# main.net
KiCad netlist of a schematic drawn in Altium Designer
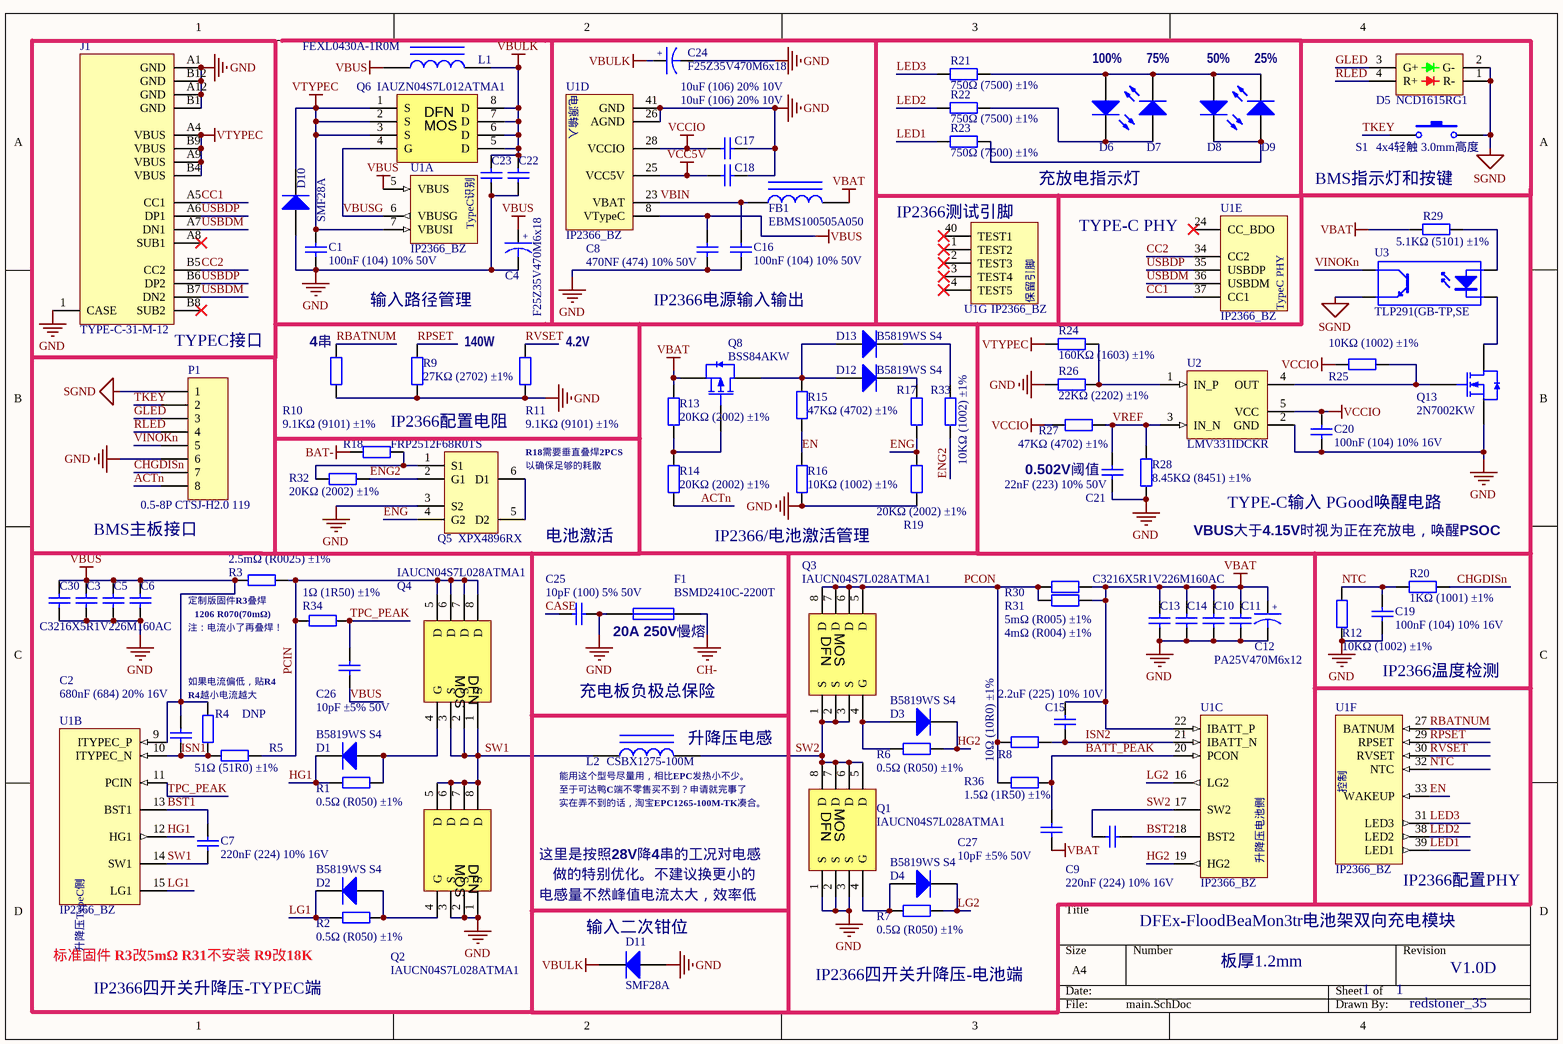
[diagram p0: main.SchDoc]

(export (version "E")
  (design (tool "Eeschema 10.0.6"))
  (components
    (comp (ref "C1")
      (value "100nF (104) 10% 50V")
      (footprint "0402_C")
      (description "贴片电容")
      (libsource (lib "Miscellaneous Devices LC") (part "0402 100nF (104) 10% 16V"))
    )
    (comp (ref "C2")
      (value "680nF (684) 20% 16V")
      (footprint "0402_C")
      (description "贴片电容")
      (libsource (lib "Miscellaneous Devices LC") (part "0402 470nF (474) 10% 10V"))
    )
    (comp (ref "C3")
      (value "C3216X5R1V226M160AC")
      (footprint "1206C")
      (description "1206尺寸TDK MLCC 35V 22uF")
      (fields (field (name "PUBLISHER") "Altium Limited"))
      (libsource (lib "山猫的集成库20190318") (part "Cap"))
    )
    (comp (ref "C4")
      (value "F25Z35V470M6x18")
      (footprint "ElecCap_Hori")
      (description "直插艾华固态电容，耐压35V容量470uF，尺寸D6.3x18")
      (libsource (lib "山猫的集成库20190318") (part "CAP2"))
    )
    (comp (ref "C5")
      (value "C3216X5R1V226M160AC")
      (footprint "1206C")
      (description "1206尺寸TDK MLCC 35V 22uF")
      (fields (field (name "PUBLISHER") "Altium Limited"))
      (libsource (lib "山猫的集成库20190318") (part "Cap"))
    )
    (comp (ref "C6")
      (value "C3216X5R1V226M160AC")
      (footprint "1206C")
      (description "1206尺寸TDK MLCC 35V 22uF")
      (fields (field (name "PUBLISHER") "Altium Limited"))
      (libsource (lib "山猫的集成库20190318") (part "Cap"))
    )
    (comp (ref "C7")
      (value "220nF (224) 10% 16V")
      (footprint "0402_C")
      (description "贴片电容")
      (libsource (lib "Miscellaneous Devices LC") (part "0402 220nF (224) 10% 16V"))
    )
    (comp (ref "C8")
      (value "470NF (474) 10% 50V")
      (footprint "0402_C")
      (description "贴片电容")
      (libsource (lib "Miscellaneous Devices LC") (part "0402 1.0uF (105) 10% 25V"))
    )
    (comp (ref "C9")
      (value "220nF (224) 10% 16V")
      (footprint "0402_C")
      (description "贴片电容")
      (libsource (lib "Miscellaneous Devices LC") (part "0402 220nF (224) 10% 16V"))
    )
    (comp (ref "C10")
      (value "C3216X5R1V226M160AC")
      (footprint "1206C")
      (description "1206尺寸TDK MLCC 35V 22uF")
      (fields (field (name "PUBLISHER") "Altium Limited"))
      (libsource (lib "山猫的集成库20190318") (part "Cap"))
    )
    (comp (ref "C11")
      (value "C3216X5R1V226M160AC")
      (footprint "1206C")
      (description "1206尺寸TDK MLCC 35V 22uF")
      (fields (field (name "PUBLISHER") "Altium Limited"))
      (libsource (lib "山猫的集成库20190318") (part "Cap"))
    )
    (comp (ref "C12")
      (value "PA25V470M6x12")
      (footprint "ElecCap_Hori")
      (description "直插固态电容，耐压25V容量470uF，尺寸D6.3x12")
      (libsource (lib "山猫的集成库20190318") (part "CAP2"))
    )
    (comp (ref "C13")
      (value "C3216X5R1V226M160AC")
      (footprint "1206C")
      (description "1206尺寸TDK MLCC 35V 22uF")
      (fields (field (name "PUBLISHER") "Altium Limited"))
      (libsource (lib "山猫的集成库20190318") (part "Cap"))
    )
    (comp (ref "C14")
      (value "C3216X5R1V226M160AC")
      (footprint "1206C")
      (description "1206尺寸TDK MLCC 35V 22uF")
      (fields (field (name "PUBLISHER") "Altium Limited"))
      (libsource (lib "山猫的集成库20190318") (part "Cap"))
    )
    (comp (ref "C15")
      (value "2.2uF (225) 10% 10V")
      (footprint "0402_C")
      (description "贴片电容")
      (libsource (lib "Miscellaneous Devices LC") (part "0402 1.0uF (105) 10% 25V"))
    )
    (comp (ref "C16")
      (value "100nF (104) 10% 50V")
      (footprint "0402_C")
      (description "贴片电容")
      (libsource (lib "Miscellaneous Devices LC") (part "0402 100nF (104) 10% 16V"))
    )
    (comp (ref "C17")
      (value "10uF (106) 20% 10V")
      (footprint "0402_C")
      (description "贴片电容")
      (libsource (lib "Miscellaneous Devices LC") (part "0402 10uF (106) 20% 6.3V"))
    )
    (comp (ref "C18")
      (value "10uF (106) 20% 10V")
      (footprint "0402_C")
      (description "贴片电容")
      (libsource (lib "Miscellaneous Devices LC") (part "0402 10uF (106) 20% 6.3V"))
    )
    (comp (ref "C19")
      (value "100nF (104) 10% 16V")
      (footprint "0402_C")
      (description "贴片电容")
      (libsource (lib "Miscellaneous Devices LC") (part "0402 100nF (104) 10% 16V"))
    )
    (comp (ref "C20")
      (value "100nF (104) 10% 16V")
      (footprint "0402_C")
      (description "贴片电容")
      (libsource (lib "Miscellaneous Devices LC") (part "0402 100nF (104) 10% 16V"))
    )
    (comp (ref "C21")
      (value "22nF (223) 10% 50V")
      (footprint "0402_C")
      (description "贴片电容")
      (libsource (lib "Miscellaneous Devices LC") (part "0402 22nF (223) 10% 50V"))
    )
    (comp (ref "C22")
      (value "C3216X5R1V226M160AC")
      (footprint "1206C")
      (description "1206尺寸TDK MLCC 35V 22uF")
      (fields (field (name "PUBLISHER") "Altium Limited"))
      (libsource (lib "山猫的集成库20190318") (part "Cap"))
    )
    (comp (ref "C23")
      (value "C3216X5R1V226M160AC")
      (footprint "1206C")
      (description "1206尺寸TDK MLCC 35V 22uF")
      (fields (field (name "PUBLISHER") "Altium Limited"))
      (libsource (lib "山猫的集成库20190318") (part "Cap"))
    )
    (comp (ref "C24")
      (value "F25Z35V470M6x18")
      (footprint "ElecCap_Hori")
      (description "直插艾华固态电容，耐压35V容量470uF，尺寸D6.3x18")
      (libsource (lib "山猫的集成库20190318") (part "CAP2"))
    )
    (comp (ref "C25")
      (value "10pF (100) 5% 50V")
      (footprint "0402_C")
      (description "贴片电容")
      (libsource (lib "Miscellaneous Devices LC") (part "0402 10pF (100) 5% 50V"))
    )
    (comp (ref "C26")
      (value "10pF ±5% 50V")
      (footprint "0402_C")
      (description "贴片电容")
      (libsource (lib "Miscellaneous Devices LC") (part "0402 1nF (102) 10% 50V"))
    )
    (comp (ref "C27")
      (value "10pF ±5% 50V")
      (footprint "0402_C")
      (description "贴片电容")
      (libsource (lib "Miscellaneous Devices LC") (part "0402 1nF (102) 10% 50V"))
    )
    (comp (ref "C30")
      (value "C3216X5R1V226M160AC")
      (footprint "1206C")
      (description "1206尺寸TDK MLCC 35V 22uF")
      (fields (field (name "PUBLISHER") "Altium Limited"))
      (libsource (lib "山猫的集成库20190318") (part "Cap"))
    )
    (comp (ref "D1")
      (value "B5819WS S4")
      (footprint "SOD-323")
      (description "二极管")
      (libsource (lib "Miscellaneous Devices LC") (part "SOD-323 1N4148WS T4"))
    )
    (comp (ref "D2")
      (value "B5819WS S4")
      (footprint "SOD-323")
      (description "二极管")
      (libsource (lib "Miscellaneous Devices LC") (part "SOD-323 1N4148WS T4"))
    )
    (comp (ref "D3")
      (value "B5819WS S4")
      (footprint "SOD-323")
      (description "二极管")
      (libsource (lib "Miscellaneous Devices LC") (part "SOD-323 1N4148WS T4"))
    )
    (comp (ref "D4")
      (value "B5819WS S4")
      (footprint "SOD-323")
      (description "二极管")
      (libsource (lib "Miscellaneous Devices LC") (part "SOD-323 1N4148WS T4"))
    )
    (comp (ref "D5")
      (value "NCD1615RG1")
      (footprint "LED-SMD_4P-L1.6-W1.5-TL-1")
      (description "国星光电 0606(1615) 尺寸 双色LED 红色/翠绿")
      (libsource (lib "custom") (part "0606DualColor LED"))
    )
    (comp (ref "D6")
      (value "蓝灯 0603")
      (footprint "0603_LED_S1")
      (description "发光二极管")
      (libsource (lib "Miscellaneous Devices LC") (part "0603 蓝灯"))
    )
    (comp (ref "D7")
      (value "蓝灯 0603")
      (footprint "0603_LED_S1")
      (description "发光二极管")
      (libsource (lib "Miscellaneous Devices LC") (part "0603 蓝灯"))
    )
    (comp (ref "D8")
      (value "蓝灯 0603")
      (footprint "0603_LED_S1")
      (description "发光二极管")
      (libsource (lib "Miscellaneous Devices LC") (part "0603 蓝灯"))
    )
    (comp (ref "D9")
      (value "蓝灯 0603")
      (footprint "0603_LED_S1")
      (description "发光二极管")
      (libsource (lib "Miscellaneous Devices LC") (part "0603 蓝灯"))
    )
    (comp (ref "D10")
      (value "SMF28A")
      (footprint "SOD-123")
      (description "SOD123封装单向TVS二极管 28V反向截止电压 峰值脉冲电流4.4A@10/1000us")
      (libsource (lib "Miscellaneous Devices LC") (part "SOD-123 B5819W  SL"))
    )
    (comp (ref "D11")
      (value "SMF28A")
      (footprint "SOD-123")
      (description "SOD123封装单向TVS二极管 28V反向截止电压 峰值脉冲电流4.4A@10/1000us")
      (libsource (lib "Miscellaneous Devices LC") (part "SOD-123 B5819W  SL"))
    )
    (comp (ref "D12")
      (value "B5819WS S4")
      (footprint "SOD-323")
      (description "二极管")
      (libsource (lib "Miscellaneous Devices LC") (part "SOD-323 1N4148WS T4"))
    )
    (comp (ref "D13")
      (value "B5819WS S4")
      (footprint "SOD-323")
      (description "二极管")
      (libsource (lib "Miscellaneous Devices LC") (part "SOD-323 1N4148WS T4"))
    )
    (comp (ref "F1")
      (value "BSMD2410C-2200T")
      (footprint "Fuse6126")
      (description "2410尺寸 20A 250V 一次性 慢速熔断陶瓷保险丝")
      (fields (field (name "PUBLISHER") "Altium Limited"))
      (libsource (lib "Miscellaneous Devices") (part "Fuse 1"))
    )
    (comp (ref "FB1")
      (value "EBMS100505A050")
      (footprint "0402_L")
      (description "贴片磁珠 200mA 5R±25% 100MHz")
      (libsource (lib "Miscellaneous Devices LC") (part "0402 12nH  5%"))
    )
    (comp (ref "J1")
      (value "TYPE-C-31-M-12")
      (footprint "USB-C-SMD_KH-TYPE-C-16P")
      (description "16Pin TypeC卧式贴片座子，韩国韩荣")
      (libsource (lib "custom") (part "KH-TYPEC-16P"))
    )
    (comp (ref "L1")
      (value "FEXL0430A-1R0M")
      (footprint "XAL4020-xxxME")
      (description "长江微电一体成型电感，1.0uH±20% 14.6mΩ DCR 9.8A饱和电流")
      (fields (field (name "PUBLISHER") "Altium Limited"))
      (libsource (lib "Miscellaneous Devices") (part "Inductor Iron"))
    )
    (comp (ref "L2")
      (value "CSBX1275-100M")
      (footprint "CSBX1275")
      (description "科达嘉电子扁线一体成型电感，13.8*12.8*7.3mm，10uH 21.0A 8.77mΩ")
      (fields (field (name "PUBLISHER") "Altium Limited"))
      (libsource (lib "Miscellaneous Devices") (part "Inductor Iron"))
    )
    (comp (ref "P1")
      (value "0.5-8P CTSJ-H2.0 119")
      (footprint "FPC0.5 2H-WS-8P")
      (description "FFC/FPC连接器 间距：0.5mm，P数：8P，卧贴，抽屉式上接，厚度H2.0mm")
      (fields (field (name "PUBLISHER") "Altium Limited"))
      (libsource (lib "山猫的集成库20190318") (part "CON 8"))
    )
    (comp (ref "Q1")
      (value "IAUCN04S7L028ATMA1")
      (footprint "SON/DFN5x6(MOS)")
      (description "40V, N-Ch, 2.80mΩ max, Automotive MOSFET, SSO8(5x6), OptiMOS™ 7")
      (libsource (lib "custom") (part "SON/DFN5x6 MOS"))
    )
    (comp (ref "Q2")
      (value "IAUCN04S7L028ATMA1")
      (footprint "SON/DFN5x6(MOS)")
      (description "40V, N-Ch, 2.80mΩ max, Automotive MOSFET, SSO8(5x6), OptiMOS™ 7")
      (libsource (lib "") (part "SON/DFN5x6 MOS_2"))
    )
    (comp (ref "Q3")
      (value "IAUCN04S7L028ATMA1")
      (footprint "SON/DFN5x6(MOS)")
      (description "40V, N-Ch, 2.80mΩ max, Automotive MOSFET, SSO8(5x6), OptiMOS™ 7")
      (libsource (lib "custom") (part "SON/DFN5x6 MOS"))
    )
    (comp (ref "Q4")
      (value "IAUCN04S7L028ATMA1")
      (footprint "SON/DFN5x6(MOS)")
      (description "40V, N-Ch, 2.80mΩ max, Automotive MOSFET, SSO8(5x6), OptiMOS™ 7")
      (libsource (lib "") (part "SON/DFN5x6 MOS_2"))
    )
    (comp (ref "Q5")
      (value "XPX4896RX")
      (footprint "EDFN3x3")
      (description "双N沟道MOSFET, DFN3x3 40V 45A 7.2mΩ")
      (libsource (lib "custom") (part "XPX10H03RX"))
    )
    (comp (ref "Q6")
      (value "IAUZN04S7L012ATMA1")
      (footprint "DFN-8_L3.0-W3.0-P0.65-BL")
      (description "OptiMOS 7 40V Logic Level Power MOSFET, 1.55mΩ @ 4.5V LL,S3O8(PDFN3333) Package")
      (libsource (lib "") (part "SON/DFN5x6 MOS_1"))
    )
    (comp (ref "Q8")
      (value "BSS84AKW")
      (footprint "SC70-3")
      (description "单P沟道小信号MOSFET(场效应管)")
      (libsource (lib "Miscellaneous Devices LC") (part "SI2301CDS-T1-GE3"))
    )
    (comp (ref "Q13")
      (value "2N7002KW")
      (footprint "SC70-3")
      (description "单N沟道MOSFET(场效应管)")
      (libsource (lib "Miscellaneous Devices LC") (part "2N7002 7002"))
    )
    (comp (ref "R1")
      (value "0.5Ω (R050) ±1%")
      (footprint "0603_R")
      (description "贴片电阻")
      (libsource (lib "Miscellaneous Devices LC") (part "0603 0Ω (0R0) 1%"))
    )
    (comp (ref "R2")
      (value "0.5Ω (R050) ±1%")
      (footprint "0603_R")
      (description "贴片电阻")
      (libsource (lib "Miscellaneous Devices LC") (part "0603 0Ω (0R0) 1%"))
    )
    (comp (ref "R3")
      (value "2.5mΩ (R0025) ±1%")
      (footprint "1206_R")
      (description "1206贴片合金检流电阻 2.5mΩ")
      (libsource (lib "Miscellaneous Devices LC") (part "1206 0Ω (0R0) 1%"))
    )
    (comp (ref "R4")
      (value "DNP")
      (footprint "0402_R")
      (description "贴片电阻(暂时空置)")
      (libsource (lib "Miscellaneous Devices LC") (part "0402 3.3KΩ (3301) 1%"))
    )
    (comp (ref "R5")
      (value "51Ω (51R0) ±1%")
      (footprint "0402_R")
      (description "贴片电阻")
      (libsource (lib "Miscellaneous Devices LC") (part "0402 51Ω (51R0) 1%"))
    )
    (comp (ref "R6")
      (value "0.5Ω (R050) ±1%")
      (footprint "0603_R")
      (description "贴片电阻")
      (libsource (lib "Miscellaneous Devices LC") (part "0603 0Ω (0R0) 1%"))
    )
    (comp (ref "R7")
      (value "0.5Ω (R050) ±1%")
      (footprint "0603_R")
      (description "贴片电阻")
      (libsource (lib "Miscellaneous Devices LC") (part "0603 0Ω (0R0) 1%"))
    )
    (comp (ref "R8")
      (value "10Ω (10R0) ±1%")
      (footprint "0402_R")
      (description "贴片电阻")
      (libsource (lib "Miscellaneous Devices LC") (part "0402 10Ω (10R0) 1%"))
    )
    (comp (ref "R9")
      (value "27KΩ (2702) ±1%")
      (footprint "0402_R")
      (description "贴片电阻")
      (libsource (lib "Miscellaneous Devices LC") (part "0402 18KΩ (1802) 1%"))
    )
    (comp (ref "R10")
      (value "9.1KΩ (9101) ±1%")
      (footprint "0402_R")
      (description "贴片电阻")
      (libsource (lib "Miscellaneous Devices LC") (part "0402 10KΩ (1002) 1%"))
    )
    (comp (ref "R11")
      (value "9.1KΩ (9101) ±1%")
      (footprint "0402_R")
      (description "贴片电阻")
      (libsource (lib "Miscellaneous Devices LC") (part "0402 10KΩ (1002) 1%"))
    )
    (comp (ref "R12")
      (value "10KΩ (1002) ±1%")
      (footprint "0402_R")
      (description "贴片电阻")
      (libsource (lib "Miscellaneous Devices LC") (part "0402 10KΩ (1002) 1%"))
    )
    (comp (ref "R13")
      (value "20KΩ (2002) ±1%")
      (footprint "0402_R")
      (description "贴片电阻")
      (libsource (lib "") (part "0402 20KΩ (2002) 1%_1"))
    )
    (comp (ref "R14")
      (value "20KΩ (2002) ±1%")
      (footprint "0402_R")
      (description "贴片电阻")
      (libsource (lib "") (part "0402 20KΩ (2002) 1%_1"))
    )
    (comp (ref "R15")
      (value "47KΩ (4702) ±1%")
      (footprint "0402_R")
      (description "贴片电阻")
      (libsource (lib "Miscellaneous Devices LC") (part "0402 47KΩ (4702) 1%"))
    )
    (comp (ref "R16")
      (value "10KΩ (1002) ±1%")
      (footprint "0402_R")
      (description "贴片电阻")
      (libsource (lib "Miscellaneous Devices LC") (part "0402 10KΩ (1002) 1%"))
    )
    (comp (ref "R17")
      (value "10KΩ (1002) ±1%")
      (footprint "0402_R")
      (description "贴片电阻")
      (libsource (lib "Miscellaneous Devices LC") (part "0402 10KΩ (1002) 1%"))
    )
    (comp (ref "R18")
      (value "FRP2512F68R0TS")
      (footprint "2512")
      (description "高功率2512封装厚膜电阻 68Ω ±1% 2W")
      (fields (field (name "PUBLISHER") "Altium Limited"))
      (libsource (lib "山猫的集成库20190318") (part "Res"))
    )
    (comp (ref "R19")
      (value "20KΩ (2002) ±1%")
      (footprint "0402_R")
      (description "贴片电阻")
      (libsource (lib "") (part "0402 20KΩ (2002) 1%_1"))
    )
    (comp (ref "R20")
      (value "1KΩ (1001) ±1%")
      (footprint "0402_R")
      (description "贴片电阻")
      (libsource (lib "Miscellaneous Devices LC") (part "0402 1KΩ (1001) 1%"))
    )
    (comp (ref "R21")
      (value "750Ω (7500) ±1%")
      (footprint "0402_R")
      (description "贴片电阻")
      (libsource (lib "Miscellaneous Devices LC") (part "0402 200Ω (2000) 1%"))
    )
    (comp (ref "R22")
      (value "750Ω (7500) ±1%")
      (footprint "0402_R")
      (description "贴片电阻")
      (libsource (lib "Miscellaneous Devices LC") (part "0402 200Ω (2000) 1%"))
    )
    (comp (ref "R23")
      (value "750Ω (7500) ±1%")
      (footprint "0402_R")
      (description "贴片电阻")
      (libsource (lib "Miscellaneous Devices LC") (part "0402 200Ω (2000) 1%"))
    )
    (comp (ref "R24")
      (value "160KΩ (1603) ±1%")
      (footprint "0402_R")
      (description "贴片电阻")
      (libsource (lib "Miscellaneous Devices LC") (part "0402 100KΩ (1003) 1%"))
    )
    (comp (ref "R25")
      (value "10KΩ (1002) ±1%")
      (footprint "0402_R")
      (description "贴片电阻")
      (libsource (lib "") (part "0402 10KΩ (1002) 1%_1"))
    )
    (comp (ref "R26")
      (value "22KΩ (2202) ±1%")
      (footprint "0402_R")
      (description "贴片电阻")
      (libsource (lib "Miscellaneous Devices LC") (part "0402 22KΩ (2202) 1%"))
    )
    (comp (ref "R27")
      (value "47KΩ (4702) ±1%")
      (footprint "0402_R")
      (description "贴片电阻")
      (libsource (lib "") (part "0402 47KΩ (4702) 1%_1"))
    )
    (comp (ref "R28")
      (value "8.45KΩ (8451) ±1%")
      (footprint "0402_R")
      (description "贴片电阻")
      (libsource (lib "Miscellaneous Devices LC") (part "0402 10KΩ (1002) 1%"))
    )
    (comp (ref "R29")
      (value "5.1KΩ (5101) ±1%")
      (footprint "0603_R")
      (description "贴片电阻")
      (libsource (lib "Miscellaneous Devices LC") (part "0603 4.7KΩ (4701) 1%"))
    )
    (comp (ref "R30")
      (value "5mΩ (R005) ±1%")
      (footprint "1206_R")
      (description "贴片合金检流电阻")
      (libsource (lib "Miscellaneous Devices LC") (part "1206 0Ω (0R0) 1%"))
    )
    (comp (ref "R31")
      (value "4mΩ (R004) ±1%")
      (footprint "1206_R")
      (description "贴片合金检流电阻")
      (libsource (lib "Miscellaneous Devices LC") (part "1206 0Ω (0R0) 1%"))
    )
    (comp (ref "R32")
      (value "20KΩ (2002) ±1%")
      (footprint "0402_R")
      (description "贴片电阻")
      (libsource (lib "Miscellaneous Devices LC") (part "0402 20KΩ (2002) 1%"))
    )
    (comp (ref "R33")
      (value "10KΩ (1002) ±1%")
      (footprint "0402_R")
      (description "贴片电阻")
      (libsource (lib "Miscellaneous Devices LC") (part "0402 10KΩ (1002) 1%"))
    )
    (comp (ref "R34")
      (value "1Ω (1R50) ±1%")
      (footprint "0402_R")
      (description "贴片电阻")
      (libsource (lib "") (part "0402 51Ω (51R0) 1%_1"))
    )
    (comp (ref "R36")
      (value "1.5Ω (1R50) ±1%")
      (footprint "0402_R")
      (description "贴片电阻")
      (libsource (lib "") (part "0402 51Ω (51R0) 1%_1"))
    )
    (comp (ref "S1")
      (value "4x4轻触 3.0mm高度")
      (footprint "SW-SMD_4P-L5.2-W5.2-P3.70-LS6.4")
      (description "4x4mm锅仔片结构金属轻触开关 H3.0mm")
      (fields (field (name "PUBLISHER") "Altium Limited"))
      (libsource (lib "Miscellaneous Devices") (part "SW-PB"))
    )
    (comp (ref "U1")
      (value "IP2366_BZ")
      (footprint "QFN40-IP2366")
      (description "支持多种快充协议，最高140W功率的充放电管理SoC")
      (libsource (lib "custom") (part "IP2366_BZ"))
    )
    (comp (ref "U2")
      (value "LMV331IDCKR")
      (footprint "SC70-5")
      (description "单路通用低电压比较器，2.7-5.5V，SC70-5封装")
      (libsource (lib "custom") (part "LMV331IDCKR"))
    )
    (comp (ref "U3")
      (value "TLP291(GB-TP,SE")
      (footprint "SOP127P700X210-4M")
      (description "DC输入 光电耦合隔离器 隔离电压(rms):3750V SOP-4封装")
      (fields (field (name "PUBLISHER") "Altium Limited"))
      (libsource (lib "Miscellaneous Devices") (part "Optoisolator1"))
    )
  )
  (nets
    (net (code "1") (name "/ACTn") (class "Default")
      (node (ref "P1") (pin "8") (pinfunction "8_8") (pintype "passive"))
      (node (ref "R14") (pin "1") (pinfunction "1_1") (pintype "passive"))
    )
    (net (code "2") (name "/BATT_PEAK") (class "Default")
      (node (ref "C27") (pin "2") (pinfunction "2_2") (pintype "passive"))
      (node (ref "R36") (pin "1") (pinfunction "1_1") (pintype "passive"))
      (node (ref "U1") (pin "20") (pinfunction "PCON_20") (pintype "input"))
    )
    (net (code "3") (name "/BST1") (class "Default")
      (node (ref "C7") (pin "2") (pinfunction "2_2") (pintype "passive"))
      (node (ref "U1") (pin "13") (pinfunction "BST1_13") (pintype "power_in"))
    )
    (net (code "4") (name "/BST2") (class "Default")
      (node (ref "C9") (pin "2") (pinfunction "2_2") (pintype "passive"))
      (node (ref "U1") (pin "18") (pinfunction "BST2_18") (pintype "power_in"))
    )
    (net (code "5") (name "/CASE") (class "Default")
      (node (ref "C25") (pin "1") (pinfunction "1_1") (pintype "passive"))
    )
    (net (code "6") (name "/CC1") (class "Default")
      (node (ref "J1") (pin "A5") (pinfunction "CC1_A5") (pintype "passive"))
      (node (ref "U1") (pin "37") (pinfunction "CC1_37") (pintype "passive"))
    )
    (net (code "7") (name "/CC2") (class "Default")
      (node (ref "J1") (pin "B5") (pinfunction "CC2_B5") (pintype "passive"))
      (node (ref "U1") (pin "34") (pinfunction "CC2_34") (pintype "passive"))
    )
    (net (code "8") (name "/CHGDISn") (class "Default")
      (node (ref "P1") (pin "7") (pinfunction "7_7") (pintype "passive"))
      (node (ref "R20") (pin "2") (pinfunction "2_2") (pintype "passive"))
    )
    (net (code "9") (name "/EN") (class "Default")
      (node (ref "R15") (pin "1") (pinfunction "1_1") (pintype "passive"))
      (node (ref "R16") (pin "2") (pinfunction "2_2") (pintype "passive"))
      (node (ref "U1") (pin "33") (pinfunction "WAKEUP_33") (pintype "input"))
    )
    (net (code "10") (name "/ENG") (class "Default")
      (node (ref "Q5") (pin "4") (pinfunction "G2_4") (pintype "passive"))
      (node (ref "R17") (pin "1") (pinfunction "1_1") (pintype "passive"))
      (node (ref "R19") (pin "2") (pinfunction "2_2") (pintype "passive"))
    )
    (net (code "11") (name "/ENG2") (class "Default")
      (node (ref "Q5") (pin "2") (pinfunction "G1_2") (pintype "passive"))
      (node (ref "R32") (pin "2") (pinfunction "2_2") (pintype "passive"))
      (node (ref "R33") (pin "1") (pinfunction "1_1") (pintype "passive"))
    )
    (net (code "12") (name "/GLED") (class "Default")
      (node (ref "D5") (pin "3") (pinfunction "G+_3") (pintype "passive"))
      (node (ref "P1") (pin "3") (pinfunction "3_3") (pintype "passive"))
    )
    (net (code "13") (name "/HG1") (class "Default")
      (node (ref "D1") (pin "2") (pinfunction "K_2") (pintype "passive"))
      (node (ref "R1") (pin "1") (pinfunction "1_1") (pintype "passive"))
      (node (ref "U1") (pin "12") (pinfunction "HG1_12") (pintype "output"))
    )
    (net (code "14") (name "/HG2") (class "Default")
      (node (ref "D3") (pin "2") (pinfunction "K_2") (pintype "passive"))
      (node (ref "R6") (pin "2") (pinfunction "2_2") (pintype "passive"))
      (node (ref "U1") (pin "19") (pinfunction "HG2_19") (pintype "output"))
    )
    (net (code "15") (name "/ISN1") (class "Default")
      (node (ref "C2") (pin "1") (pinfunction "1_1") (pintype "passive"))
      (node (ref "R4") (pin "1") (pinfunction "1_1") (pintype "passive"))
      (node (ref "R5") (pin "1") (pinfunction "1_1") (pintype "passive"))
      (node (ref "U1") (pin "10") (pinfunction "ITYPEC_N_10") (pintype "input"))
    )
    (net (code "16") (name "/ISN2") (class "Default")
      (node (ref "C15") (pin "1") (pinfunction "1_1") (pintype "passive"))
      (node (ref "R8") (pin "2") (pinfunction "2_2") (pintype "passive"))
      (node (ref "U1") (pin "21") (pinfunction "IBATT_N_21") (pintype "input"))
    )
    (net (code "17") (name "/LED1") (class "Default")
      (node (ref "R23") (pin "1") (pinfunction "1_1") (pintype "passive"))
      (node (ref "U1") (pin "39") (pinfunction "LED1_39") (pintype "output"))
    )
    (net (code "18") (name "/LED2") (class "Default")
      (node (ref "R22") (pin "1") (pinfunction "1_1") (pintype "passive"))
      (node (ref "U1") (pin "38") (pinfunction "LED2_38") (pintype "output"))
    )
    (net (code "19") (name "/LED3") (class "Default")
      (node (ref "R21") (pin "1") (pinfunction "1_1") (pintype "passive"))
      (node (ref "U1") (pin "31") (pinfunction "LED3_31") (pintype "output"))
    )
    (net (code "20") (name "/LG1") (class "Default")
      (node (ref "D2") (pin "2") (pinfunction "K_2") (pintype "passive"))
      (node (ref "R2") (pin "1") (pinfunction "1_1") (pintype "passive"))
      (node (ref "U1") (pin "15") (pinfunction "LG1_15") (pintype "power_in"))
    )
    (net (code "21") (name "/LG2") (class "Default")
      (node (ref "D4") (pin "2") (pinfunction "K_2") (pintype "passive"))
      (node (ref "R7") (pin "2") (pinfunction "2_2") (pintype "passive"))
      (node (ref "U1") (pin "16") (pinfunction "LG2_16") (pintype "output"))
    )
    (net (code "22") (name "/NTC") (class "Default")
      (node (ref "C19") (pin "2") (pinfunction "2_2") (pintype "passive"))
      (node (ref "R12") (pin "2") (pinfunction "2_2") (pintype "passive"))
      (node (ref "R20") (pin "1") (pinfunction "1_1") (pintype "passive"))
      (node (ref "U1") (pin "32") (pinfunction "NTC_32") (pintype "input"))
    )
    (net (code "23") (name "/PCIN") (class "Default")
      (node (ref "Q4") (pin "5") (pinfunction "D_5") (pintype "passive"))
      (node (ref "Q4") (pin "6") (pinfunction "D_6") (pintype "passive"))
      (node (ref "Q4") (pin "7") (pinfunction "D_7") (pintype "passive"))
      (node (ref "Q4") (pin "8") (pinfunction "D_8") (pintype "passive"))
      (node (ref "R3") (pin "2") (pinfunction "2_2") (pintype "passive"))
      (node (ref "R34") (pin "2") (pinfunction "2_2") (pintype "passive"))
      (node (ref "R5") (pin "2") (pinfunction "2_2") (pintype "passive"))
    )
    (net (code "24") (name "/PCON") (class "Default")
      (node (ref "Q3") (pin "5") (pinfunction "D_5") (pintype "passive"))
      (node (ref "Q3") (pin "6") (pinfunction "D_6") (pintype "passive"))
      (node (ref "Q3") (pin "7") (pinfunction "D_7") (pintype "passive"))
      (node (ref "Q3") (pin "8") (pinfunction "D_8") (pintype "passive"))
      (node (ref "R30") (pin "1") (pinfunction "1_1") (pintype "passive"))
      (node (ref "R31") (pin "1") (pinfunction "1_1") (pintype "passive"))
      (node (ref "R36") (pin "2") (pinfunction "2_2") (pintype "passive"))
      (node (ref "R8") (pin "1") (pinfunction "1_1") (pintype "passive"))
    )
    (net (code "25") (name "/RBATNUM") (class "Default")
      (node (ref "R10") (pin "2") (pinfunction "2_2") (pintype "passive"))
      (node (ref "U1") (pin "27") (pinfunction "BATNUM_27") (pintype "input"))
    )
    (net (code "26") (name "/RLED") (class "Default")
      (node (ref "D5") (pin "4") (pinfunction "R+_4") (pintype "passive"))
      (node (ref "P1") (pin "4") (pinfunction "4_4") (pintype "passive"))
    )
    (net (code "27") (name "/RPSET") (class "Default")
      (node (ref "R9") (pin "2") (pinfunction "2_2") (pintype "passive"))
      (node (ref "U1") (pin "29") (pinfunction "RPSET_29") (pintype "input"))
    )
    (net (code "28") (name "/RVSET") (class "Default")
      (node (ref "R11") (pin "2") (pinfunction "2_2") (pintype "passive"))
      (node (ref "U1") (pin "30") (pinfunction "RVSET_30") (pintype "input"))
    )
    (net (code "29") (name "/SW1") (class "Default")
      (node (ref "C7") (pin "1") (pinfunction "1_1") (pintype "passive"))
      (node (ref "L2") (pin "1") (pinfunction "1_1") (pintype "passive"))
      (node (ref "Q2") (pin "5") (pinfunction "D_5") (pintype "passive"))
      (node (ref "Q2") (pin "6") (pinfunction "D_6") (pintype "passive"))
      (node (ref "Q2") (pin "7") (pinfunction "D_7") (pintype "passive"))
      (node (ref "Q2") (pin "8") (pinfunction "D_8") (pintype "passive"))
      (node (ref "Q4") (pin "1") (pinfunction "S_1") (pintype "passive"))
      (node (ref "Q4") (pin "2") (pinfunction "S_2") (pintype "passive"))
      (node (ref "Q4") (pin "3") (pinfunction "S_3") (pintype "passive"))
      (node (ref "U1") (pin "14") (pinfunction "SW1_14") (pintype "power_in"))
    )
    (net (code "30") (name "/SW2") (class "Default")
      (node (ref "C9") (pin "1") (pinfunction "1_1") (pintype "passive"))
      (node (ref "L2") (pin "2") (pinfunction "2_2") (pintype "passive"))
      (node (ref "Q1") (pin "5") (pinfunction "D_5") (pintype "passive"))
      (node (ref "Q1") (pin "6") (pinfunction "D_6") (pintype "passive"))
      (node (ref "Q1") (pin "7") (pinfunction "D_7") (pintype "passive"))
      (node (ref "Q1") (pin "8") (pinfunction "D_8") (pintype "passive"))
      (node (ref "Q3") (pin "1") (pinfunction "S_1") (pintype "passive"))
      (node (ref "Q3") (pin "2") (pinfunction "S_2") (pintype "passive"))
      (node (ref "Q3") (pin "3") (pinfunction "S_3") (pintype "passive"))
      (node (ref "U1") (pin "17") (pinfunction "SW2_17") (pintype "power_in"))
    )
    (net (code "31") (name "/TKEY") (class "Default")
      (node (ref "P1") (pin "2") (pinfunction "2_2") (pintype "passive"))
      (node (ref "S1") (pin "1") (pinfunction "1_1") (pintype "passive"))
    )
    (net (code "32") (name "/TPC_PEAK") (class "Default")
      (node (ref "C26") (pin "2") (pinfunction "2_2") (pintype "passive"))
      (node (ref "R34") (pin "1") (pinfunction "1_1") (pintype "passive"))
      (node (ref "U1") (pin "11") (pinfunction "PCIN_11") (pintype "input"))
    )
    (net (code "33") (name "/USBDM") (class "Default")
      (node (ref "J1") (pin "A7") (pinfunction "DN1_A7") (pintype "passive"))
      (node (ref "J1") (pin "B7") (pinfunction "DN2_B7") (pintype "passive"))
      (node (ref "U1") (pin "36") (pinfunction "USBDM_36") (pintype "passive"))
    )
    (net (code "34") (name "/USBDP") (class "Default")
      (node (ref "J1") (pin "A6") (pinfunction "DP1_A6") (pintype "passive"))
      (node (ref "J1") (pin "B6") (pinfunction "DP2_B6") (pintype "passive"))
      (node (ref "U1") (pin "35") (pinfunction "USBDP_35") (pintype "passive"))
    )
    (net (code "35") (name "/VBIN") (class "Default")
      (node (ref "C16") (pin "2") (pinfunction "2_2") (pintype "passive"))
      (node (ref "FB1") (pin "1") (pinfunction "1_1") (pintype "passive"))
      (node (ref "U1") (pin "23") (pinfunction "VBAT_23") (pintype "power_in"))
    )
    (net (code "36") (name "/VBUSG") (class "Default")
      (node (ref "Q6") (pin "4") (pinfunction "G_4") (pintype "passive"))
      (node (ref "U1") (pin "6") (pinfunction "VBUSG_6") (pintype "output"))
    )
    (net (code "37") (name "/VINOKn") (class "Default")
      (node (ref "P1") (pin "5") (pinfunction "5_5") (pintype "passive"))
      (node (ref "U3") (pin "4") (pinfunction "C_4") (pintype "passive"))
    )
    (net (code "38") (name "/VREF") (class "Default")
      (node (ref "C21") (pin "2") (pinfunction "2_2") (pintype "passive"))
      (node (ref "R27") (pin "2") (pinfunction "2_2") (pintype "passive"))
      (node (ref "R28") (pin "2") (pinfunction "2_2") (pintype "passive"))
      (node (ref "U2") (pin "3") (pinfunction "IN_N_3") (pintype "input"))
    )
    (net (code "39") (name "BAT-") (class "Default")
      (node (ref "R18") (pin "1") (pinfunction "1_1") (pintype "passive"))
    )
    (net (code "40") (name "CH-") (class "Default")
      (node (ref "F1") (pin "2") (pinfunction "2_2") (pintype "passive"))
    )
    (net (code "41") (name "GND") (class "Default")
      (node (ref "C1") (pin "1") (pinfunction "1_1") (pintype "passive"))
      (node (ref "C10") (pin "1") (pinfunction "1_1") (pintype "passive"))
      (node (ref "C11") (pin "1") (pinfunction "1_1") (pintype "passive"))
      (node (ref "C12") (pin "2") (pinfunction "2_2") (pintype "passive"))
      (node (ref "C13") (pin "1") (pinfunction "1_1") (pintype "passive"))
      (node (ref "C14") (pin "1") (pinfunction "1_1") (pintype "passive"))
      (node (ref "C16") (pin "1") (pinfunction "1_1") (pintype "passive"))
      (node (ref "C17") (pin "2") (pinfunction "2_2") (pintype "passive"))
      (node (ref "C18") (pin "2") (pinfunction "2_2") (pintype "passive"))
      (node (ref "C19") (pin "1") (pinfunction "1_1") (pintype "passive"))
      (node (ref "C20") (pin "1") (pinfunction "1_1") (pintype "passive"))
      (node (ref "C21") (pin "1") (pinfunction "1_1") (pintype "passive"))
      (node (ref "C22") (pin "1") (pinfunction "1_1") (pintype "passive"))
      (node (ref "C23") (pin "1") (pinfunction "1_1") (pintype "passive"))
      (node (ref "C24") (pin "2") (pinfunction "2_2") (pintype "passive"))
      (node (ref "C25") (pin "2") (pinfunction "2_2") (pintype "passive"))
      (node (ref "C3") (pin "1") (pinfunction "1_1") (pintype "passive"))
      (node (ref "C30") (pin "1") (pinfunction "1_1") (pintype "passive"))
      (node (ref "C4") (pin "2") (pinfunction "2_2") (pintype "passive"))
      (node (ref "C5") (pin "1") (pinfunction "1_1") (pintype "passive"))
      (node (ref "C6") (pin "1") (pinfunction "1_1") (pintype "passive"))
      (node (ref "C8") (pin "1") (pinfunction "1_1") (pintype "passive"))
      (node (ref "D10") (pin "1") (pinfunction "A_1") (pintype "passive"))
      (node (ref "D11") (pin "1") (pinfunction "A_1") (pintype "passive"))
      (node (ref "F1") (pin "1") (pinfunction "1_1") (pintype "passive"))
      (node (ref "J1") (pin "1") (pinfunction "CASE_1") (pintype "passive"))
      (node (ref "J1") (pin "A1") (pinfunction "GND_A1") (pintype "passive"))
      (node (ref "J1") (pin "A12") (pinfunction "GND_A12") (pintype "passive"))
      (node (ref "J1") (pin "B1") (pinfunction "GND_B1") (pintype "passive"))
      (node (ref "J1") (pin "B12") (pinfunction "GND_B12") (pintype "passive"))
      (node (ref "P1") (pin "6") (pinfunction "6_6") (pintype "passive"))
      (node (ref "Q1") (pin "1") (pinfunction "S_1") (pintype "passive"))
      (node (ref "Q1") (pin "2") (pinfunction "S_2") (pintype "passive"))
      (node (ref "Q1") (pin "3") (pinfunction "S_3") (pintype "passive"))
      (node (ref "Q13") (pin "2") (pinfunction "S_2") (pintype "passive"))
      (node (ref "Q2") (pin "1") (pinfunction "S_1") (pintype "passive"))
      (node (ref "Q2") (pin "2") (pinfunction "S_2") (pintype "passive"))
      (node (ref "Q2") (pin "3") (pinfunction "S_3") (pintype "passive"))
      (node (ref "Q5") (pin "3") (pinfunction "S2_3") (pintype "passive"))
      (node (ref "R10") (pin "1") (pinfunction "1_1") (pintype "passive"))
      (node (ref "R11") (pin "1") (pinfunction "1_1") (pintype "passive"))
      (node (ref "R12") (pin "1") (pinfunction "1_1") (pintype "passive"))
      (node (ref "R16") (pin "1") (pinfunction "1_1") (pintype "passive"))
      (node (ref "R19") (pin "1") (pinfunction "1_1") (pintype "passive"))
      (node (ref "R26") (pin "1") (pinfunction "1_1") (pintype "passive"))
      (node (ref "R28") (pin "1") (pinfunction "1_1") (pintype "passive"))
      (node (ref "R9") (pin "1") (pinfunction "1_1") (pintype "passive"))
      (node (ref "U1") (pin "26") (pinfunction "AGND_26") (pintype "power_in"))
      (node (ref "U1") (pin "41") (pinfunction "GND_41") (pintype "power_in"))
      (node (ref "U2") (pin "2") (pinfunction "GND_2") (pintype "power_in"))
    )
    (net (code "42") (name "Net-(D1-A)") (class "Default")
      (node (ref "D1") (pin "1") (pinfunction "A_1") (pintype "passive"))
      (node (ref "Q4") (pin "4") (pinfunction "G_4") (pintype "passive"))
      (node (ref "R1") (pin "2") (pinfunction "2_2") (pintype "passive"))
    )
    (net (code "43") (name "Net-(D2-A)") (class "Default")
      (node (ref "D2") (pin "1") (pinfunction "A_1") (pintype "passive"))
      (node (ref "Q2") (pin "4") (pinfunction "G_4") (pintype "passive"))
      (node (ref "R2") (pin "2") (pinfunction "2_2") (pintype "passive"))
    )
    (net (code "44") (name "Net-(D3-A)") (class "Default")
      (node (ref "D3") (pin "1") (pinfunction "A_1") (pintype "passive"))
      (node (ref "Q3") (pin "4") (pinfunction "G_4") (pintype "passive"))
      (node (ref "R6") (pin "1") (pinfunction "1_1") (pintype "passive"))
    )
    (net (code "45") (name "Net-(D4-A)") (class "Default")
      (node (ref "D4") (pin "1") (pinfunction "A_1") (pintype "passive"))
      (node (ref "Q1") (pin "4") (pinfunction "G_4") (pintype "passive"))
      (node (ref "R7") (pin "1") (pinfunction "1_1") (pintype "passive"))
    )
    (net (code "46") (name "Net-(D6-PadA)") (class "Default")
      (node (ref "D6") (pin "A") (pinfunction "A_A") (pintype "passive"))
      (node (ref "D7") (pin "K") (pinfunction "K_K") (pintype "passive"))
      (node (ref "D8") (pin "A") (pinfunction "A_A") (pintype "passive"))
      (node (ref "D9") (pin "K") (pinfunction "K_K") (pintype "passive"))
      (node (ref "R21") (pin "2") (pinfunction "2_2") (pintype "passive"))
    )
    (net (code "47") (name "Net-(D6-PadK)") (class "Default")
      (node (ref "D6") (pin "K") (pinfunction "K_K") (pintype "passive"))
      (node (ref "D7") (pin "A") (pinfunction "A_A") (pintype "passive"))
      (node (ref "R22") (pin "2") (pinfunction "2_2") (pintype "passive"))
    )
    (net (code "48") (name "Net-(D8-PadK)") (class "Default")
      (node (ref "D8") (pin "K") (pinfunction "K_K") (pintype "passive"))
      (node (ref "D9") (pin "A") (pinfunction "A_A") (pintype "passive"))
      (node (ref "R23") (pin "2") (pinfunction "2_2") (pintype "passive"))
    )
    (net (code "49") (name "Net-(D12-A)") (class "Default")
      (node (ref "D12") (pin "1") (pinfunction "A_1") (pintype "passive"))
      (node (ref "D13") (pin "1") (pinfunction "A_1") (pintype "passive"))
      (node (ref "Q8") (pin "3") (pinfunction "D_3") (pintype "passive"))
      (node (ref "R15") (pin "2") (pinfunction "2_2") (pintype "passive"))
    )
    (net (code "50") (name "Net-(D12-K)") (class "Default")
      (node (ref "D12") (pin "2") (pinfunction "K_2") (pintype "passive"))
      (node (ref "R17") (pin "2") (pinfunction "2_2") (pintype "passive"))
    )
    (net (code "51") (name "Net-(D13-K)") (class "Default")
      (node (ref "D13") (pin "2") (pinfunction "K_2") (pintype "passive"))
      (node (ref "R33") (pin "2") (pinfunction "2_2") (pintype "passive"))
    )
    (net (code "52") (name "Net-(Q5-D1)") (class "Default")
      (node (ref "Q5") (pin "5") (pinfunction "D2_5") (pintype "passive"))
      (node (ref "Q5") (pin "6") (pinfunction "D1_6") (pintype "passive"))
    )
    (net (code "53") (name "Net-(Q5-S1)") (class "Default")
      (node (ref "Q5") (pin "1") (pinfunction "S1_1") (pintype "passive"))
      (node (ref "R18") (pin "2") (pinfunction "2_2") (pintype "passive"))
      (node (ref "R32") (pin "1") (pinfunction "1_1") (pintype "passive"))
    )
    (net (code "54") (name "Net-(Q8-G)") (class "Default")
      (node (ref "Q8") (pin "1") (pinfunction "G_1") (pintype "passive"))
      (node (ref "R13") (pin "1") (pinfunction "1_1") (pintype "passive"))
      (node (ref "R14") (pin "2") (pinfunction "2_2") (pintype "passive"))
    )
    (net (code "55") (name "Net-(Q13-D)") (class "Default")
      (node (ref "Q13") (pin "3") (pinfunction "D_3") (pintype "passive"))
      (node (ref "U3") (pin "2") (pinfunction "K_2") (pintype "passive"))
    )
    (net (code "56") (name "Net-(Q13-G)") (class "Default")
      (node (ref "Q13") (pin "1") (pinfunction "G_1") (pintype "passive"))
      (node (ref "R25") (pin "1") (pinfunction "1_1") (pintype "passive"))
      (node (ref "U2") (pin "4") (pinfunction "OUT_4") (pintype "open_collector"))
    )
    (net (code "57") (name "Net-(U2-IN_P)") (class "Default")
      (node (ref "R24") (pin "2") (pinfunction "2_2") (pintype "passive"))
      (node (ref "R26") (pin "2") (pinfunction "2_2") (pintype "passive"))
      (node (ref "U2") (pin "1") (pinfunction "IN_P_1") (pintype "input"))
    )
    (net (code "58") (name "Net-(U3-A)") (class "Default")
      (node (ref "R29") (pin "2") (pinfunction "2_2") (pintype "passive"))
      (node (ref "U3") (pin "1") (pinfunction "A_1") (pintype "passive"))
    )
    (net (code "59") (name "SGND") (class "Default")
      (node (ref "D5") (pin "1") (pinfunction "R-_1") (pintype "passive"))
      (node (ref "D5") (pin "2") (pinfunction "G-_2") (pintype "passive"))
      (node (ref "P1") (pin "1") (pinfunction "1_1") (pintype "passive"))
      (node (ref "S1") (pin "2") (pinfunction "2_2") (pintype "passive"))
      (node (ref "U3") (pin "3") (pinfunction "E_3") (pintype "passive"))
    )
    (net (code "60") (name "VBAT") (class "Default")
      (node (ref "C10") (pin "2") (pinfunction "2_2") (pintype "passive"))
      (node (ref "C11") (pin "2") (pinfunction "2_2") (pintype "passive"))
      (node (ref "C12") (pin "1") (pinfunction "1_1") (pintype "passive"))
      (node (ref "C13") (pin "2") (pinfunction "2_2") (pintype "passive"))
      (node (ref "C14") (pin "2") (pinfunction "2_2") (pintype "passive"))
      (node (ref "C15") (pin "2") (pinfunction "2_2") (pintype "passive"))
      (node (ref "C27") (pin "1") (pinfunction "1_1") (pintype "passive"))
      (node (ref "FB1") (pin "2") (pinfunction "2_2") (pintype "passive"))
      (node (ref "Q8") (pin "2") (pinfunction "S_2") (pintype "passive"))
      (node (ref "R13") (pin "2") (pinfunction "2_2") (pintype "passive"))
      (node (ref "R29") (pin "1") (pinfunction "1_1") (pintype "passive"))
      (node (ref "R30") (pin "2") (pinfunction "2_2") (pintype "passive"))
      (node (ref "R31") (pin "2") (pinfunction "2_2") (pintype "passive"))
      (node (ref "U1") (pin "22") (pinfunction "IBATT_P_22") (pintype "input"))
    )
    (net (code "61") (name "VBULK") (class "Default")
      (node (ref "C22") (pin "2") (pinfunction "2_2") (pintype "passive"))
      (node (ref "C23") (pin "2") (pinfunction "2_2") (pintype "passive"))
      (node (ref "C24") (pin "1") (pinfunction "1_1") (pintype "passive"))
      (node (ref "D11") (pin "2") (pinfunction "K_2") (pintype "passive"))
      (node (ref "L1") (pin "2") (pinfunction "2_2") (pintype "passive"))
      (node (ref "Q6") (pin "5") (pinfunction "D_5") (pintype "passive"))
      (node (ref "Q6") (pin "6") (pinfunction "D_6") (pintype "passive"))
      (node (ref "Q6") (pin "7") (pinfunction "D_7") (pintype "passive"))
      (node (ref "Q6") (pin "8") (pinfunction "D_8") (pintype "passive"))
    )
    (net (code "62") (name "VBUS") (class "Default")
      (node (ref "C2") (pin "2") (pinfunction "2_2") (pintype "passive"))
      (node (ref "C26") (pin "1") (pinfunction "1_1") (pintype "passive"))
      (node (ref "C3") (pin "2") (pinfunction "2_2") (pintype "passive"))
      (node (ref "C30") (pin "2") (pinfunction "2_2") (pintype "passive"))
      (node (ref "C4") (pin "1") (pinfunction "1_1") (pintype "passive"))
      (node (ref "C5") (pin "2") (pinfunction "2_2") (pintype "passive"))
      (node (ref "C6") (pin "2") (pinfunction "2_2") (pintype "passive"))
      (node (ref "C8") (pin "2") (pinfunction "2_2") (pintype "passive"))
      (node (ref "L1") (pin "1") (pinfunction "1_1") (pintype "passive"))
      (node (ref "R3") (pin "1") (pinfunction "1_1") (pintype "passive"))
      (node (ref "R4") (pin "2") (pinfunction "2_2") (pintype "passive"))
      (node (ref "U1") (pin "5") (pinfunction "VBUS_5") (pintype "input"))
      (node (ref "U1") (pin "8") (pinfunction "VTypeC_8") (pintype "power_in"))
      (node (ref "U1") (pin "9") (pinfunction "ITYPEC_P_9") (pintype "input"))
    )
    (net (code "63") (name "VCC5V") (class "Default")
      (node (ref "C18") (pin "1") (pinfunction "1_1") (pintype "passive"))
      (node (ref "U1") (pin "25") (pinfunction "VCC5V_25") (pintype "power_in"))
    )
    (net (code "64") (name "VCCIO") (class "Default")
      (node (ref "C17") (pin "1") (pinfunction "1_1") (pintype "passive"))
      (node (ref "C20") (pin "2") (pinfunction "2_2") (pintype "passive"))
      (node (ref "R25") (pin "2") (pinfunction "2_2") (pintype "passive"))
      (node (ref "R27") (pin "1") (pinfunction "1_1") (pintype "passive"))
      (node (ref "U1") (pin "28") (pinfunction "VCCIO_28") (pintype "power_in"))
      (node (ref "U2") (pin "5") (pinfunction "VCC_5") (pintype "power_in"))
    )
    (net (code "65") (name "VTYPEC") (class "Default")
      (node (ref "C1") (pin "2") (pinfunction "2_2") (pintype "passive"))
      (node (ref "D10") (pin "2") (pinfunction "K_2") (pintype "passive"))
      (node (ref "J1") (pin "A4") (pinfunction "VBUS_A4") (pintype "passive"))
      (node (ref "J1") (pin "A9") (pinfunction "VBUS_A9") (pintype "passive"))
      (node (ref "J1") (pin "B4") (pinfunction "VBUS_B4") (pintype "passive"))
      (node (ref "J1") (pin "B9") (pinfunction "VBUS_B9") (pintype "passive"))
      (node (ref "Q6") (pin "1") (pinfunction "S_1") (pintype "passive"))
      (node (ref "Q6") (pin "2") (pinfunction "S_2") (pintype "passive"))
      (node (ref "Q6") (pin "3") (pinfunction "S_3") (pintype "passive"))
      (node (ref "R24") (pin "1") (pinfunction "1_1") (pintype "passive"))
      (node (ref "U1") (pin "7") (pinfunction "VBUSI_7") (pintype "input"))
    )
    (net (code "66") (name "unconnected-(J1-SUB1-PadA8)") (class "Default")
      (node (ref "J1") (pin "A8") (pinfunction "SUB1_A8") (pintype "passive+no_connect"))
    )
    (net (code "67") (name "unconnected-(J1-SUB2-PadB8)") (class "Default")
      (node (ref "J1") (pin "B8") (pinfunction "SUB2_B8") (pintype "passive+no_connect"))
    )
    (net (code "68") (name "unconnected-(U1E-CC_BDO-Pad24)") (class "Default")
      (node (ref "U1") (pin "24") (pinfunction "CC_BDO_24") (pintype "passive+no_connect"))
    )
    (net (code "69") (name "unconnected-(U1G-TEST1-Pad40)") (class "Default")
      (node (ref "U1") (pin "40") (pinfunction "TEST1_40") (pintype "passive+no_connect"))
    )
    (net (code "70") (name "unconnected-(U1G-TEST2-Pad1)") (class "Default")
      (node (ref "U1") (pin "1") (pinfunction "TEST2_1") (pintype "passive+no_connect"))
    )
    (net (code "71") (name "unconnected-(U1G-TEST3-Pad2)") (class "Default")
      (node (ref "U1") (pin "2") (pinfunction "TEST3_2") (pintype "passive+no_connect"))
    )
    (net (code "72") (name "unconnected-(U1G-TEST4-Pad3)") (class "Default")
      (node (ref "U1") (pin "3") (pinfunction "TEST4_3") (pintype "passive+no_connect"))
    )
    (net (code "73") (name "unconnected-(U1G-TEST5-Pad4)") (class "Default")
      (node (ref "U1") (pin "4") (pinfunction "TEST5_4") (pintype "passive+no_connect"))
    )
  )
)
